# working.net
KiCad netlist of a schematic drawn in EAGLE
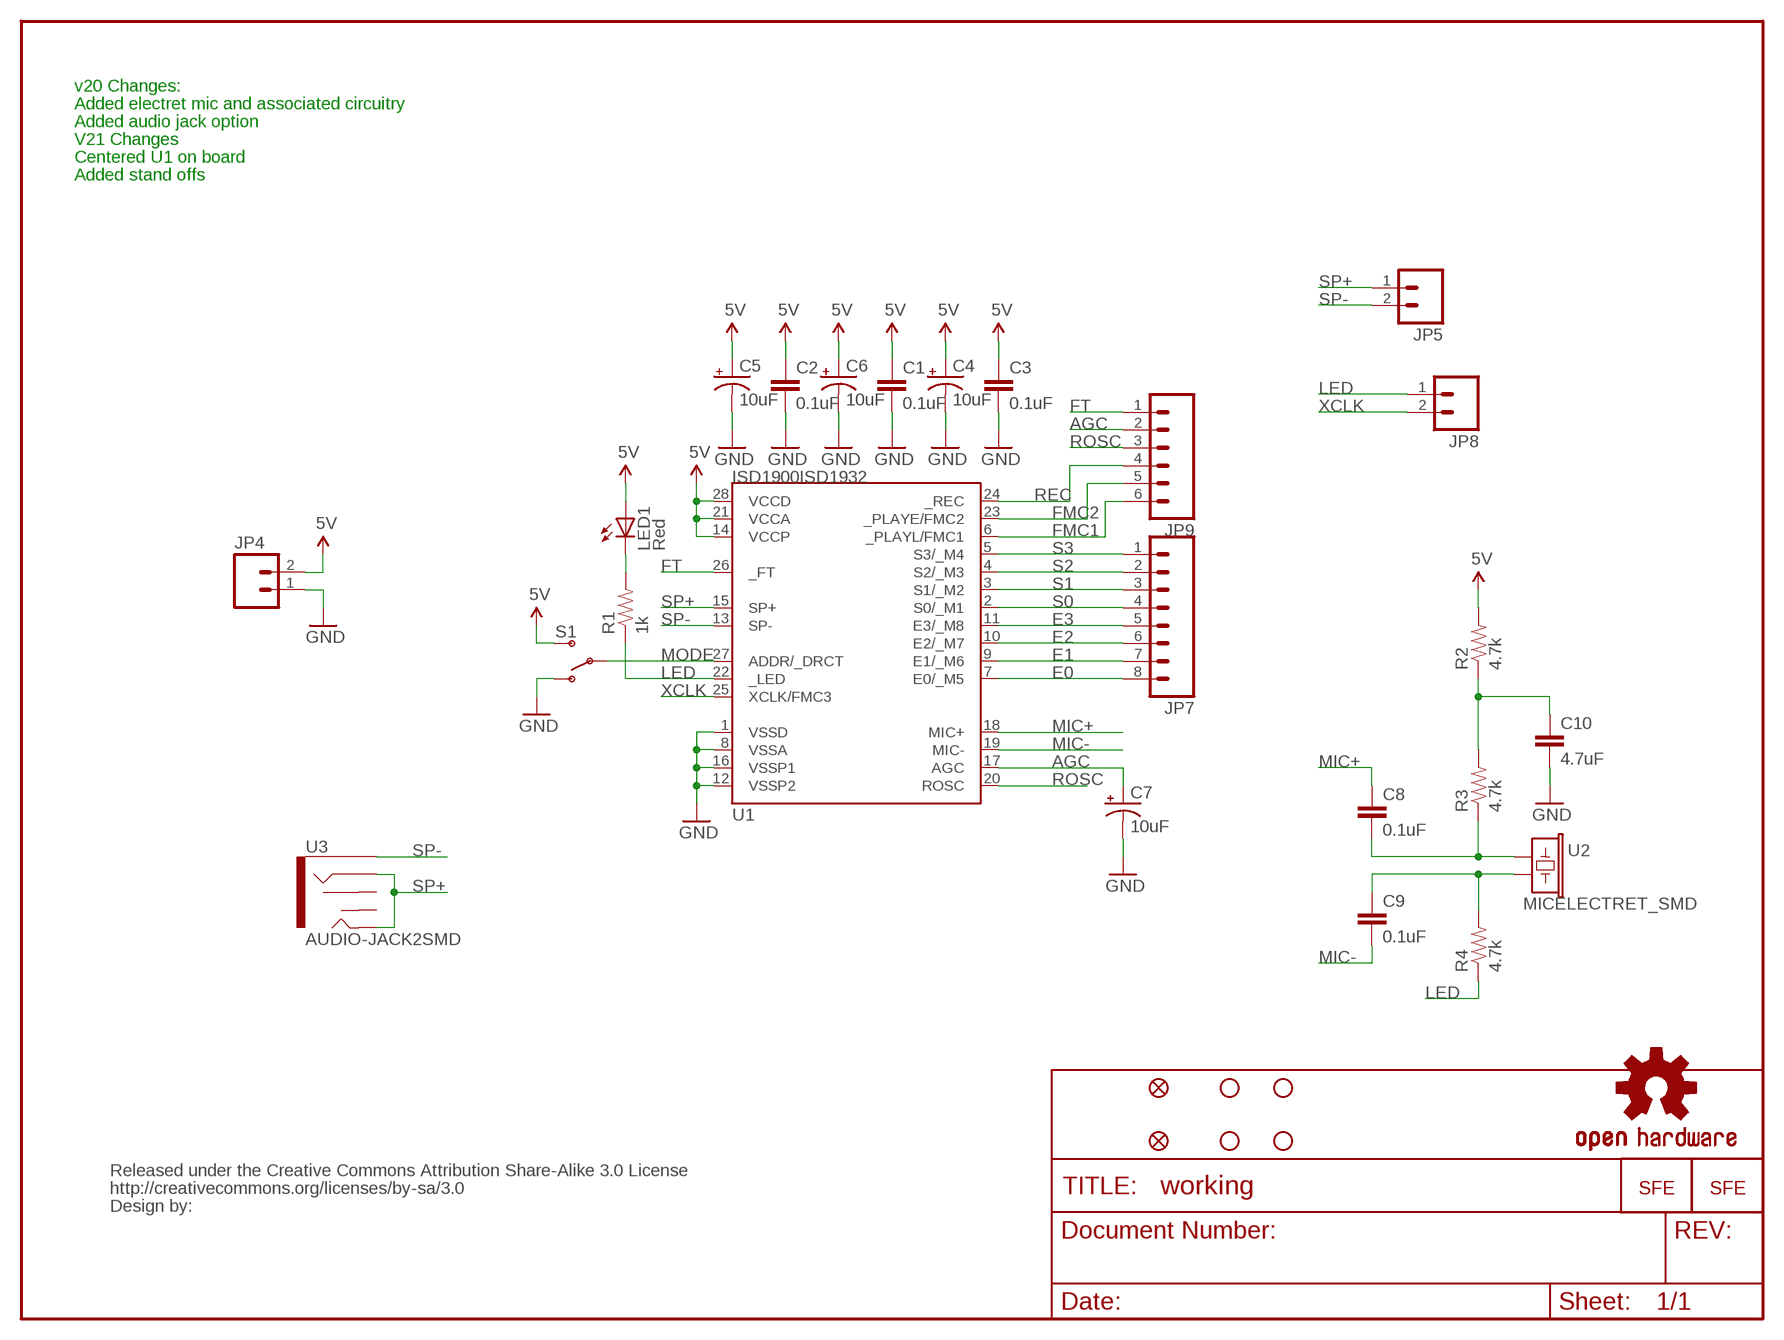
[diagram p0: schematic, sheet 1]

(export (version "E")
  (design (tool "Eeschema 10.0.6"))
  (components
    (comp (ref "C1")
      (value "0.1uF")
      (footprint "eagle-import:0603-CAP")
      (libsource (lib "eagle-import") (part "CAP0603-CAP"))
    )
    (comp (ref "C2")
      (value "0.1uF")
      (footprint "eagle-import:0603-CAP")
      (libsource (lib "eagle-import") (part "CAP0603-CAP"))
    )
    (comp (ref "C3")
      (value "0.1uF")
      (footprint "eagle-import:0603-CAP")
      (libsource (lib "eagle-import") (part "CAP0603-CAP"))
    )
    (comp (ref "C4")
      (value "10uF")
      (footprint "eagle-import:EIA3216")
      (libsource (lib "eagle-import") (part "CAP_POL1206"))
    )
    (comp (ref "C5")
      (value "10uF")
      (footprint "eagle-import:EIA3216")
      (libsource (lib "eagle-import") (part "CAP_POL1206"))
    )
    (comp (ref "C6")
      (value "10uF")
      (footprint "eagle-import:EIA3216")
      (libsource (lib "eagle-import") (part "CAP_POL1206"))
    )
    (comp (ref "C7")
      (value "10uF")
      (footprint "eagle-import:EIA3216")
      (libsource (lib "eagle-import") (part "CAP_POL1206"))
    )
    (comp (ref "C8")
      (value "0.1uF")
      (footprint "eagle-import:0603-CAP")
      (libsource (lib "eagle-import") (part "CAP0603-CAP"))
    )
    (comp (ref "C9")
      (value "0.1uF")
      (footprint "eagle-import:0603-CAP")
      (libsource (lib "eagle-import") (part "CAP0603-CAP"))
    )
    (comp (ref "C10")
      (value "4.7uF")
      (footprint "eagle-import:0603-CAP")
      (libsource (lib "eagle-import") (part "CAP0603-CAP"))
    )
    (comp (ref "JP1")
      (value "LOGO-SFENEW")
      (footprint "eagle-import:SFE-NEW-WEBLOGO")
      (libsource (lib "eagle-import") (part "LOGO-SFENEW"))
    )
    (comp (ref "JP2")
      (value "FIDUCIAL1X2")
      (footprint "eagle-import:FIDUCIAL-1X2")
      (libsource (lib "eagle-import") (part "FIDUCIAL1X2"))
    )
    (comp (ref "JP3")
      (value "FIDUCIAL1X2")
      (footprint "eagle-import:FIDUCIAL-1X2")
      (libsource (lib "eagle-import") (part "FIDUCIAL1X2"))
    )
    (comp (ref "JP4")
      (value "M02PTH")
      (footprint "eagle-import:1X02")
      (libsource (lib "eagle-import") (part "M02PTH"))
    )
    (comp (ref "JP5")
      (value "M02PTH")
      (footprint "eagle-import:1X02")
      (libsource (lib "eagle-import") (part "M02PTH"))
    )
    (comp (ref "JP6")
      (value "STAND-OFF")
      (footprint "eagle-import:STAND-OFF")
      (libsource (lib "eagle-import") (part "STAND-OFF"))
    )
    (comp (ref "JP7")
      (value "M08")
      (footprint "eagle-import:1X08")
      (libsource (lib "eagle-import") (part "M08"))
    )
    (comp (ref "JP8")
      (value "M02PTH")
      (footprint "eagle-import:1X02")
      (libsource (lib "eagle-import") (part "M02PTH"))
    )
    (comp (ref "JP9")
      (value "M06SIP")
      (footprint "eagle-import:1X06")
      (libsource (lib "eagle-import") (part "M06SIP"))
    )
    (comp (ref "JP10")
      (value "STAND-OFF")
      (footprint "eagle-import:STAND-OFF")
      (libsource (lib "eagle-import") (part "STAND-OFF"))
    )
    (comp (ref "JP11")
      (value "STAND-OFF")
      (footprint "eagle-import:STAND-OFF")
      (libsource (lib "eagle-import") (part "STAND-OFF"))
    )
    (comp (ref "JP12")
      (value "STAND-OFF")
      (footprint "eagle-import:STAND-OFF")
      (libsource (lib "eagle-import") (part "STAND-OFF"))
    )
    (comp (ref "JP13")
      (value "LOGO-SFENW2")
      (footprint "eagle-import:SFE-NEW-WEB")
      (libsource (lib "eagle-import") (part "LOGO-SFENW2"))
    )
    (comp (ref "LED1")
      (value "Red")
      (footprint "eagle-import:LED-0603")
      (libsource (lib "eagle-import") (part "LED0603"))
    )
    (comp (ref "R1")
      (value "1k")
      (footprint "eagle-import:0603-RES")
      (libsource (lib "eagle-import") (part "RESISTOR0603-RES"))
    )
    (comp (ref "R2")
      (value "4.7k")
      (footprint "eagle-import:0603-RES")
      (libsource (lib "eagle-import") (part "RESISTOR0603-RES"))
    )
    (comp (ref "R3")
      (value "4.7k")
      (footprint "eagle-import:0603-RES")
      (libsource (lib "eagle-import") (part "RESISTOR0603-RES"))
    )
    (comp (ref "R4")
      (value "4.7k")
      (footprint "eagle-import:0603-RES")
      (libsource (lib "eagle-import") (part "RESISTOR0603-RES"))
    )
    (comp (ref "S1")
      (value "SWITCH-SPSTSMD")
      (footprint "eagle-import:AYZ0202")
      (libsource (lib "eagle-import") (part "SWITCH-SPSTSMD"))
    )
    (comp (ref "U$10")
      (value "CREATIVE_COMMONS")
      (footprint "eagle-import:CREATIVE_COMMONS")
      (libsource (lib "eagle-import") (part "CREATIVE_COMMONS"))
    )
    (comp (ref "U$14")
      (value "OSHW-LOGOL")
      (footprint "eagle-import:OSHW-LOGO-L")
      (libsource (lib "eagle-import") (part "OSHW-LOGOL"))
    )
    (comp (ref "U1")
      (value "ISD1900ISD1932")
      (footprint "eagle-import:SO-28W")
      (libsource (lib "eagle-import") (part "ISD1900ISD1932"))
    )
    (comp (ref "U2")
      (value "MICELECTRET_SMD")
      (footprint "eagle-import:MIC_ELECTRET_SMD")
      (libsource (lib "eagle-import") (part "MICELECTRET_SMD"))
    )
    (comp (ref "U3")
      (value "AUDIO-JACK2SMD")
      (footprint "eagle-import:AUDIO-JACK-3.5MM-SMD")
      (libsource (lib "eagle-import") (part "AUDIO-JACK2SMD"))
    )
  )
  (nets
    (net (code "1") (name "/AGC") (class "Default")
      (node (ref "C7") (pin "A") (pinfunction "+_A") (pintype "passive"))
      (node (ref "JP9") (pin "2") (pinfunction "2_2") (pintype "passive"))
      (node (ref "U1") (pin "17") (pinfunction "AGC_17") (pintype "bidirectional"))
    )
    (net (code "2") (name "/E0") (class "Default")
      (node (ref "JP7") (pin "8") (pinfunction "8_8") (pintype "passive"))
      (node (ref "U1") (pin "7") (pinfunction "E0/_M5_7") (pintype "bidirectional"))
    )
    (net (code "3") (name "/E1") (class "Default")
      (node (ref "JP7") (pin "7") (pinfunction "7_7") (pintype "passive"))
      (node (ref "U1") (pin "9") (pinfunction "E1/_M6_9") (pintype "bidirectional"))
    )
    (net (code "4") (name "/E2") (class "Default")
      (node (ref "JP7") (pin "6") (pinfunction "6_6") (pintype "passive"))
      (node (ref "U1") (pin "10") (pinfunction "E2/_M7_10") (pintype "bidirectional"))
    )
    (net (code "5") (name "/E3") (class "Default")
      (node (ref "JP7") (pin "5") (pinfunction "5_5") (pintype "passive"))
      (node (ref "U1") (pin "11") (pinfunction "E3/_M8_11") (pintype "bidirectional"))
    )
    (net (code "6") (name "/FMC1") (class "Default")
      (node (ref "JP9") (pin "6") (pinfunction "6_6") (pintype "passive"))
      (node (ref "U1") (pin "6") (pinfunction "_PLAYL/FMC1_6") (pintype "bidirectional"))
    )
    (net (code "7") (name "/FMC2") (class "Default")
      (node (ref "JP9") (pin "5") (pinfunction "5_5") (pintype "passive"))
      (node (ref "U1") (pin "23") (pinfunction "_PLAYE/FMC2_23") (pintype "bidirectional"))
    )
    (net (code "8") (name "/FT") (class "Default")
      (node (ref "JP9") (pin "1") (pinfunction "1_1") (pintype "passive"))
      (node (ref "U1") (pin "26") (pinfunction "_FT_26") (pintype "bidirectional"))
    )
    (net (code "9") (name "/LED") (class "Default")
      (node (ref "JP8") (pin "1") (pinfunction "1_1") (pintype "passive"))
      (node (ref "R1") (pin "1") (pinfunction "1_1") (pintype "passive"))
      (node (ref "R4") (pin "1") (pinfunction "1_1") (pintype "passive"))
      (node (ref "U1") (pin "22") (pinfunction "_LED_22") (pintype "bidirectional"))
    )
    (net (code "10") (name "/MIC+") (class "Default")
      (node (ref "C8") (pin "1") (pinfunction "1_1") (pintype "passive"))
      (node (ref "U1") (pin "18") (pinfunction "MIC+_18") (pintype "bidirectional"))
    )
    (net (code "11") (name "/MIC-") (class "Default")
      (node (ref "C9") (pin "2") (pinfunction "2_2") (pintype "passive"))
      (node (ref "U1") (pin "19") (pinfunction "MIC-_19") (pintype "bidirectional"))
    )
    (net (code "12") (name "/MODE") (class "Default")
      (node (ref "S1") (pin "2") (pinfunction "P_2") (pintype "passive"))
      (node (ref "U1") (pin "27") (pinfunction "ADDR/_DRCT_27") (pintype "bidirectional"))
    )
    (net (code "13") (name "/REC") (class "Default")
      (node (ref "JP9") (pin "4") (pinfunction "4_4") (pintype "passive"))
      (node (ref "U1") (pin "24") (pinfunction "_REC_24") (pintype "bidirectional"))
    )
    (net (code "14") (name "/ROSC") (class "Default")
      (node (ref "JP9") (pin "3") (pinfunction "3_3") (pintype "passive"))
      (node (ref "U1") (pin "20") (pinfunction "ROSC_20") (pintype "bidirectional"))
    )
    (net (code "15") (name "/S0") (class "Default")
      (node (ref "JP7") (pin "4") (pinfunction "4_4") (pintype "passive"))
      (node (ref "U1") (pin "2") (pinfunction "S0/_M1_2") (pintype "bidirectional"))
    )
    (net (code "16") (name "/S1") (class "Default")
      (node (ref "JP7") (pin "3") (pinfunction "3_3") (pintype "passive"))
      (node (ref "U1") (pin "3") (pinfunction "S1/_M2_3") (pintype "bidirectional"))
    )
    (net (code "17") (name "/S2") (class "Default")
      (node (ref "JP7") (pin "2") (pinfunction "2_2") (pintype "passive"))
      (node (ref "U1") (pin "4") (pinfunction "S2/_M3_4") (pintype "bidirectional"))
    )
    (net (code "18") (name "/S3") (class "Default")
      (node (ref "JP7") (pin "1") (pinfunction "1_1") (pintype "passive"))
      (node (ref "U1") (pin "5") (pinfunction "S3/_M4_5") (pintype "bidirectional"))
    )
    (net (code "19") (name "/SP+") (class "Default")
      (node (ref "JP5") (pin "1") (pinfunction "1_1") (pintype "passive"))
      (node (ref "U1") (pin "15") (pinfunction "SP+_15") (pintype "bidirectional"))
      (node (ref "U3") (pin "RING") (pinfunction "RING_RING") (pintype "bidirectional"))
      (node (ref "U3") (pin "TIP") (pinfunction "TIP_TIP") (pintype "bidirectional"))
    )
    (net (code "20") (name "/SP-") (class "Default")
      (node (ref "JP5") (pin "2") (pinfunction "2_2") (pintype "passive"))
      (node (ref "U1") (pin "13") (pinfunction "SP-_13") (pintype "bidirectional"))
      (node (ref "U3") (pin "SLEEVE") (pinfunction "SLEEVE_SLEEVE") (pintype "bidirectional"))
    )
    (net (code "21") (name "/XCLK") (class "Default")
      (node (ref "JP8") (pin "2") (pinfunction "2_2") (pintype "passive"))
      (node (ref "U1") (pin "25") (pinfunction "XCLK/FMC3_25") (pintype "bidirectional"))
    )
    (net (code "22") (name "5V") (class "Default")
      (node (ref "C1") (pin "1") (pinfunction "1_1") (pintype "passive"))
      (node (ref "C2") (pin "1") (pinfunction "1_1") (pintype "passive"))
      (node (ref "C3") (pin "1") (pinfunction "1_1") (pintype "passive"))
      (node (ref "C4") (pin "A") (pinfunction "+_A") (pintype "passive"))
      (node (ref "C5") (pin "A") (pinfunction "+_A") (pintype "passive"))
      (node (ref "C6") (pin "A") (pinfunction "+_A") (pintype "passive"))
      (node (ref "JP4") (pin "2") (pinfunction "2_2") (pintype "passive"))
      (node (ref "LED1") (pin "A") (pinfunction "A_A") (pintype "passive"))
      (node (ref "R2") (pin "2") (pinfunction "2_2") (pintype "passive"))
      (node (ref "S1") (pin "3") (pinfunction "S_3") (pintype "passive"))
      (node (ref "U1") (pin "14") (pinfunction "VCCP_14") (pintype "bidirectional"))
      (node (ref "U1") (pin "21") (pinfunction "VCCA_21") (pintype "bidirectional"))
      (node (ref "U1") (pin "28") (pinfunction "VCCD_28") (pintype "bidirectional"))
    )
    (net (code "23") (name "GND") (class "Default")
      (node (ref "C1") (pin "2") (pinfunction "2_2") (pintype "passive"))
      (node (ref "C10") (pin "2") (pinfunction "2_2") (pintype "passive"))
      (node (ref "C2") (pin "2") (pinfunction "2_2") (pintype "passive"))
      (node (ref "C3") (pin "2") (pinfunction "2_2") (pintype "passive"))
      (node (ref "C4") (pin "C") (pinfunction "-_C") (pintype "passive"))
      (node (ref "C5") (pin "C") (pinfunction "-_C") (pintype "passive"))
      (node (ref "C6") (pin "C") (pinfunction "-_C") (pintype "passive"))
      (node (ref "C7") (pin "C") (pinfunction "-_C") (pintype "passive"))
      (node (ref "JP4") (pin "1") (pinfunction "1_1") (pintype "passive"))
      (node (ref "S1") (pin "1") (pinfunction "O_1") (pintype "passive"))
      (node (ref "U1") (pin "1") (pinfunction "VSSD_1") (pintype "bidirectional"))
      (node (ref "U1") (pin "12") (pinfunction "VSSP2_12") (pintype "bidirectional"))
      (node (ref "U1") (pin "16") (pinfunction "VSSP1_16") (pintype "bidirectional"))
      (node (ref "U1") (pin "8") (pinfunction "VSSA_8") (pintype "bidirectional"))
    )
    (net (code "24") (name "Net-(C8-Pad2)") (class "Default")
      (node (ref "C8") (pin "2") (pinfunction "2_2") (pintype "passive"))
      (node (ref "R3") (pin "1") (pinfunction "1_1") (pintype "passive"))
      (node (ref "U2") (pin "1") (pinfunction "1_1") (pintype "passive"))
    )
    (net (code "25") (name "Net-(C9-Pad1)") (class "Default")
      (node (ref "C9") (pin "1") (pinfunction "1_1") (pintype "passive"))
      (node (ref "R4") (pin "2") (pinfunction "2_2") (pintype "passive"))
      (node (ref "U2") (pin "2") (pinfunction "2_2") (pintype "passive"))
    )
    (net (code "26") (name "Net-(C10-Pad1)") (class "Default")
      (node (ref "C10") (pin "1") (pinfunction "1_1") (pintype "passive"))
      (node (ref "R2") (pin "1") (pinfunction "1_1") (pintype "passive"))
      (node (ref "R3") (pin "2") (pinfunction "2_2") (pintype "passive"))
    )
    (net (code "27") (name "Net-(LED1-PadC)") (class "Default")
      (node (ref "LED1") (pin "C") (pinfunction "C_C") (pintype "passive"))
      (node (ref "R1") (pin "2") (pinfunction "2_2") (pintype "passive"))
    )
    (net (code "28") (name "unconnected-(U3-PadRSH)") (class "Default")
      (node (ref "U3") (pin "RSH") (pinfunction "RSH_RSH") (pintype "bidirectional"))
    )
    (net (code "29") (name "unconnected-(U3-PadTSH)") (class "Default")
      (node (ref "U3") (pin "TSH") (pinfunction "TSH_TSH") (pintype "bidirectional"))
    )
  )
)
